# Shield.net
KiCad netlist of a schematic drawn in EAGLE
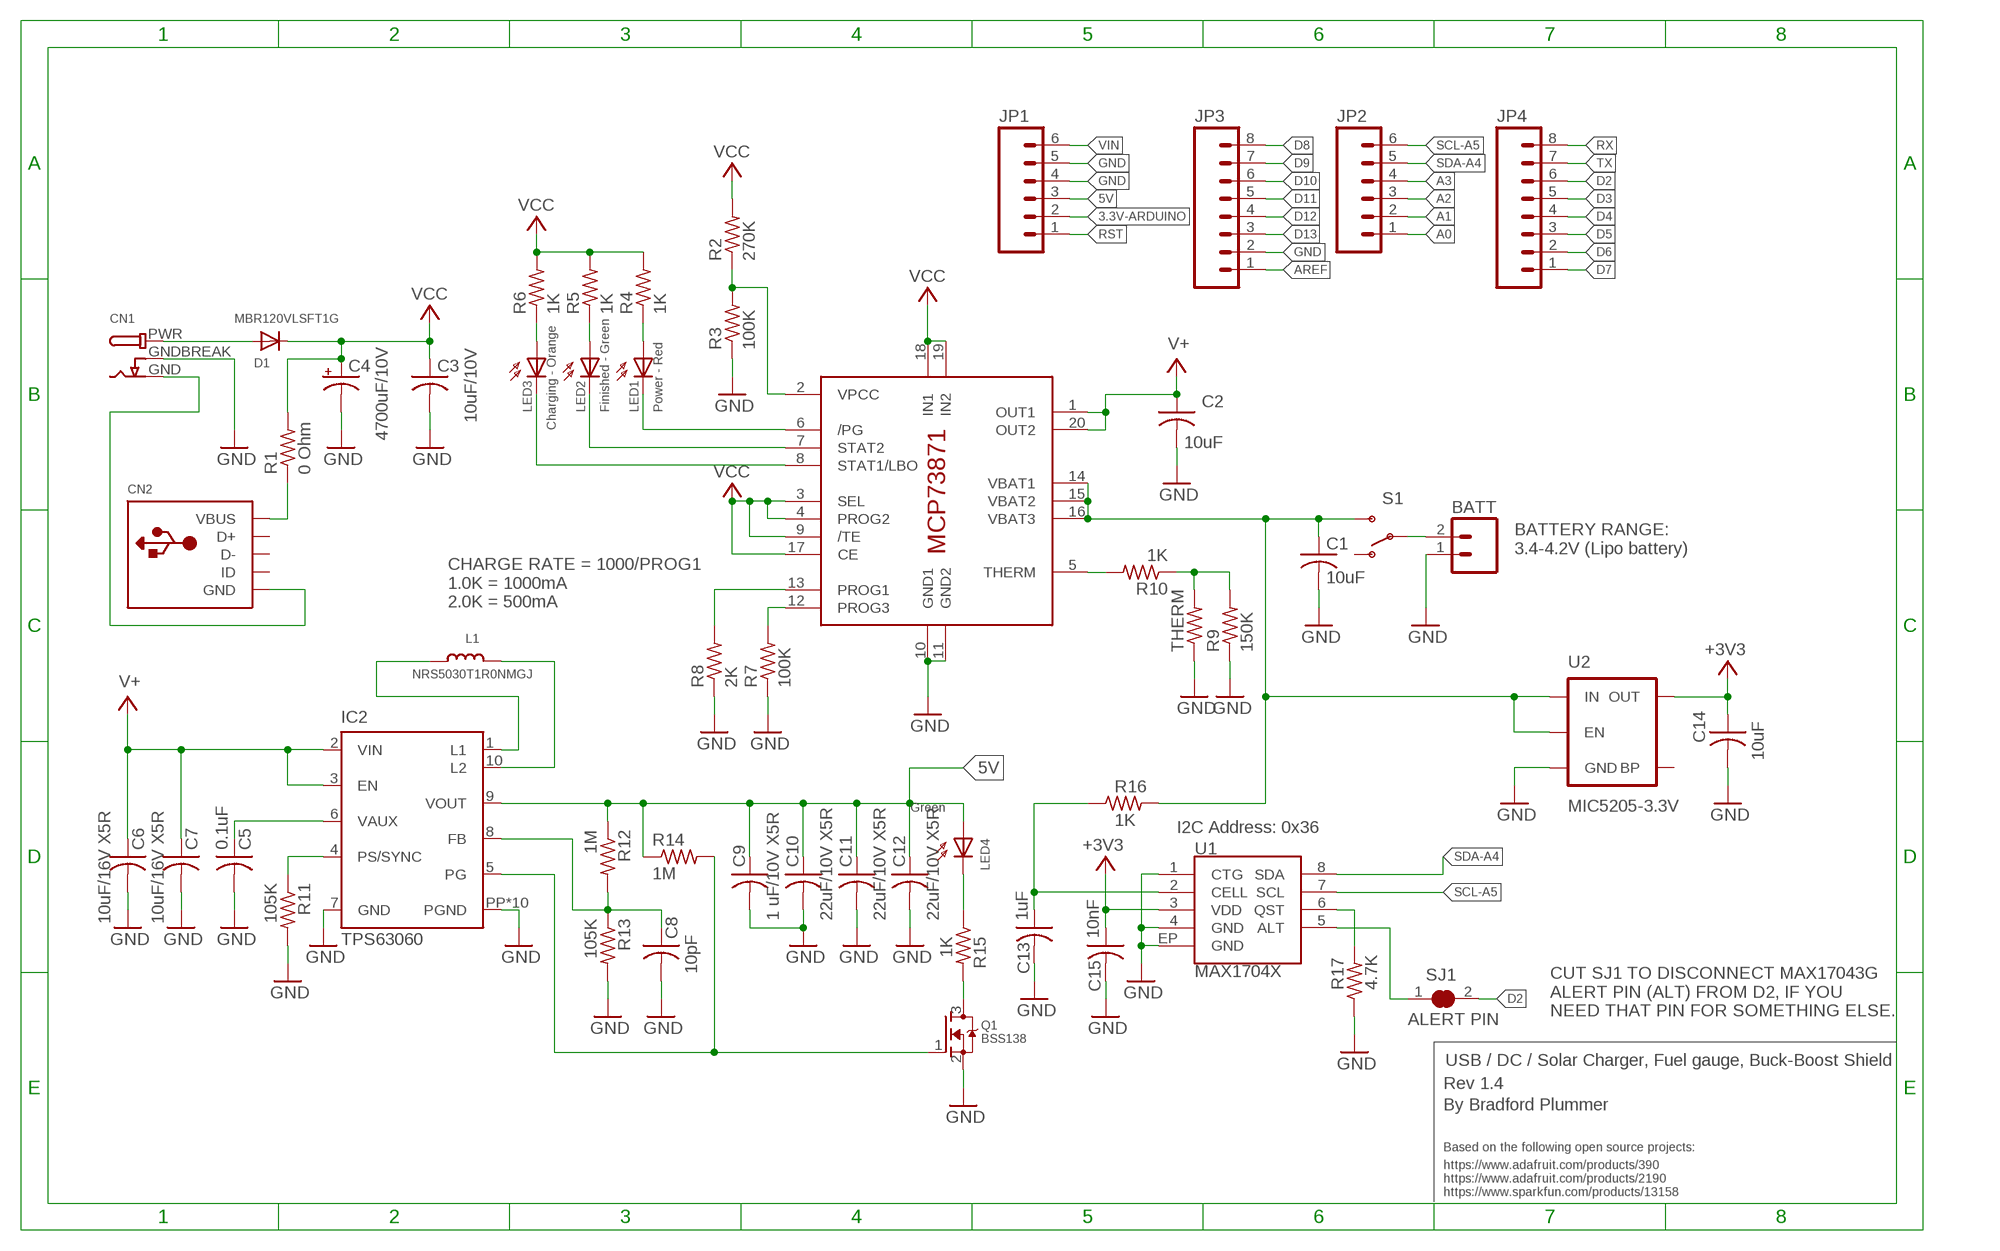
[diagram p0: schematic, sheet 1]

(export (version "E")
  (design (tool "Eeschema 10.0.6"))
  (components
    (comp (ref "BATT")
      (value "M02JST-PTH-VERT")
      (footprint "eagle-import:JST-2-PTH-VERT")
      (libsource (lib "eagle-import") (part "M02JST-PTH-VERT"))
    )
    (comp (ref "C1")
      (value "10uF")
      (footprint "eagle-import:C0805K")
      (libsource (lib "eagle-import") (part "C-USC0805K"))
    )
    (comp (ref "C2")
      (value "10uF")
      (footprint "eagle-import:C0805K")
      (libsource (lib "eagle-import") (part "C-USC0805K"))
    )
    (comp (ref "C3")
      (value "10uF/10V")
      (footprint "eagle-import:C0805K")
      (libsource (lib "eagle-import") (part "C-USC0805K"))
    )
    (comp (ref "C4")
      (value "4700uF/10V")
      (footprint "eagle-import:E5-13")
      (libsource (lib "eagle-import") (part "CPOL-USE5-13"))
    )
    (comp (ref "C5")
      (value "0.1uF")
      (footprint "eagle-import:C0805K")
      (libsource (lib "eagle-import") (part "C-USC0805K"))
    )
    (comp (ref "C6")
      (value "10uF/16V X5R")
      (footprint "eagle-import:C0805K")
      (libsource (lib "eagle-import") (part "C-USC0805K"))
    )
    (comp (ref "C7")
      (value "10uF/16V X5R")
      (footprint "eagle-import:C0805K")
      (libsource (lib "eagle-import") (part "C-USC0805K"))
    )
    (comp (ref "C8")
      (value "10pF")
      (footprint "eagle-import:C0805K")
      (libsource (lib "eagle-import") (part "C-USC0805K"))
    )
    (comp (ref "C9")
      (value "1 uF/10V X5R")
      (footprint "eagle-import:C0805K")
      (libsource (lib "eagle-import") (part "C-USC0805K"))
    )
    (comp (ref "C10")
      (value "22uF/10V X5R")
      (footprint "eagle-import:C0805K")
      (libsource (lib "eagle-import") (part "C-USC0805K"))
    )
    (comp (ref "C11")
      (value "22uF/10V X5R")
      (footprint "eagle-import:C0805K")
      (libsource (lib "eagle-import") (part "C-USC0805K"))
    )
    (comp (ref "C12")
      (value "22uF/10V X5R")
      (footprint "eagle-import:C0805K")
      (libsource (lib "eagle-import") (part "C-USC0805K"))
    )
    (comp (ref "C13")
      (value "1uF")
      (footprint "eagle-import:C0805K")
      (libsource (lib "eagle-import") (part "C-USC0805K"))
    )
    (comp (ref "C14")
      (value "10uF")
      (footprint "eagle-import:C0805K")
      (libsource (lib "eagle-import") (part "C-USC0805K"))
    )
    (comp (ref "C15")
      (value "10nF")
      (footprint "eagle-import:C0805K")
      (libsource (lib "eagle-import") (part "C-USC0805K"))
    )
    (comp (ref "CN1")
      (value "DCBARREL1.3MM")
      (footprint "eagle-import:DCJACK_1.3MM_PTH")
      (libsource (lib "eagle-import") (part "DCBARREL1.3MM"))
    )
    (comp (ref "CN2")
      (value "USBMINIB")
      (footprint "eagle-import:USB-MINIB")
      (libsource (lib "eagle-import") (part "USBMINIB"))
    )
    (comp (ref "D1")
      (value "MBR120VLSFT1G")
      (footprint "eagle-import:SOD-123")
      (libsource (lib "eagle-import") (part "DIODESOD-123"))
    )
    (comp (ref "IC1")
      (value "MCP73871")
      (footprint "eagle-import:QFN20")
      (libsource (lib "eagle-import") (part "MCP73871"))
    )
    (comp (ref "IC2")
      (value "TPS63060")
      (footprint "eagle-import:DSC-S-PWSON-N10")
      (libsource (lib "eagle-import") (part "TPS63060"))
    )
    (comp (ref "JP1")
      (value "M06NO_SILK_FEMALE_PTH")
      (footprint "eagle-import:1X06_NO_SILK")
      (libsource (lib "eagle-import") (part "M06NO_SILK_FEMALE_PTH"))
    )
    (comp (ref "JP2")
      (value "M06NO_SILK_FEMALE_PTH")
      (footprint "eagle-import:1X06_NO_SILK")
      (libsource (lib "eagle-import") (part "M06NO_SILK_FEMALE_PTH"))
    )
    (comp (ref "JP3")
      (value "M08NO_SILK_FEMALE_PTH")
      (footprint "eagle-import:1X08_NO_SILK")
      (libsource (lib "eagle-import") (part "M08NO_SILK_FEMALE_PTH"))
    )
    (comp (ref "JP4")
      (value "M08NO_SILK_FEMALE_PTH")
      (footprint "eagle-import:1X08_NO_SILK")
      (libsource (lib "eagle-import") (part "M08NO_SILK_FEMALE_PTH"))
    )
    (comp (ref "L1")
      (value "NRS5030T1R0NMGJ")
      (footprint "eagle-import:INDUCTOR_5X5MM_TDK_VLC5045")
      (libsource (lib "eagle-import") (part "INDUCTORTDK_VLC5045"))
    )
    (comp (ref "LED1")
      (value "Power - Red")
      (footprint "eagle-import:SFH205")
      (libsource (lib "eagle-import") (part "SFH205"))
    )
    (comp (ref "LED2")
      (value "Finished - Green")
      (footprint "eagle-import:SFH205")
      (libsource (lib "eagle-import") (part "SFH205"))
    )
    (comp (ref "LED3")
      (value "Charging - Orange")
      (footprint "eagle-import:SFH205")
      (libsource (lib "eagle-import") (part "SFH205"))
    )
    (comp (ref "LED4")
      (value "Green")
      (footprint "eagle-import:SFH205")
      (libsource (lib "eagle-import") (part "SFH205"))
    )
    (comp (ref "Q1")
      (value "BSS138")
      (footprint "eagle-import:SOT23-WIDE")
      (libsource (lib "eagle-import") (part "MOSFET-NWIDE"))
    )
    (comp (ref "R1")
      (value "0 Ohm")
      (footprint "eagle-import:R0805")
      (libsource (lib "eagle-import") (part "R-US_R0805"))
    )
    (comp (ref "R2")
      (value "270K")
      (footprint "eagle-import:R0805")
      (libsource (lib "eagle-import") (part "R-US_R0805"))
    )
    (comp (ref "R3")
      (value "100K")
      (footprint "eagle-import:R0805")
      (libsource (lib "eagle-import") (part "R-US_R0805"))
    )
    (comp (ref "R4")
      (value "1K")
      (footprint "eagle-import:R0805")
      (libsource (lib "eagle-import") (part "R-US_R0805"))
    )
    (comp (ref "R5")
      (value "1K")
      (footprint "eagle-import:R0805")
      (libsource (lib "eagle-import") (part "R-US_R0805"))
    )
    (comp (ref "R6")
      (value "1K")
      (footprint "eagle-import:R0805")
      (libsource (lib "eagle-import") (part "R-US_R0805"))
    )
    (comp (ref "R7")
      (value "100K")
      (footprint "eagle-import:R0805")
      (libsource (lib "eagle-import") (part "R-US_R0805"))
    )
    (comp (ref "R8")
      (value "2K")
      (footprint "eagle-import:R0805")
      (libsource (lib "eagle-import") (part "R-US_R0805"))
    )
    (comp (ref "R9")
      (value "150K")
      (footprint "eagle-import:M0805")
      (libsource (lib "eagle-import") (part "R-US_M0805"))
    )
    (comp (ref "R10")
      (value "1K")
      (footprint "eagle-import:M0805")
      (libsource (lib "eagle-import") (part "R-US_M0805"))
    )
    (comp (ref "R11")
      (value "105K")
      (footprint "eagle-import:M0805")
      (libsource (lib "eagle-import") (part "R-US_M0805"))
    )
    (comp (ref "R12")
      (value "1M")
      (footprint "eagle-import:M0805")
      (libsource (lib "eagle-import") (part "R-US_M0805"))
    )
    (comp (ref "R13")
      (value "105K")
      (footprint "eagle-import:M0805")
      (libsource (lib "eagle-import") (part "R-US_M0805"))
    )
    (comp (ref "R14")
      (value "1M")
      (footprint "eagle-import:M0805")
      (libsource (lib "eagle-import") (part "R-US_M0805"))
    )
    (comp (ref "R15")
      (value "1K")
      (footprint "eagle-import:M0805")
      (libsource (lib "eagle-import") (part "R-US_M0805"))
    )
    (comp (ref "R16")
      (value "1K")
      (footprint "eagle-import:M0805")
      (libsource (lib "eagle-import") (part "R-US_M0805"))
    )
    (comp (ref "R17")
      (value "4.7K")
      (footprint "eagle-import:M0805")
      (libsource (lib "eagle-import") (part "R-US_M0805"))
    )
    (comp (ref "S1")
      (value "SWITCH-SPDTPTH")
      (footprint "eagle-import:SWITCH-SPDT")
      (libsource (lib "eagle-import") (part "SWITCH-SPDTPTH"))
    )
    (comp (ref "SJ1")
      (value "ALERT PIN")
      (footprint "eagle-import:SJ")
      (libsource (lib "eagle-import") (part "SJ"))
    )
    (comp (ref "THERM")
      (value "R-US_FLIPFLOP")
      (footprint "eagle-import:0805-THM")
      (libsource (lib "eagle-import") (part "R-US_FLIPFLOP"))
    )
    (comp (ref "U1")
      (value "MAX1704X")
      (footprint "eagle-import:TDFN-8")
      (libsource (lib "eagle-import") (part "MAX1704X"))
    )
    (comp (ref "U2")
      (value "MIC5205-3.3V")
      (footprint "eagle-import:SOT23-5")
      (libsource (lib "eagle-import") (part "MIC52053.3V"))
    )
  )
  (nets
    (net (code "1") (name "+3V3") (class "Default")
      (node (ref "C14") (pin "1") (pinfunction "1_1") (pintype "passive"))
      (node (ref "C15") (pin "1") (pinfunction "1_1") (pintype "passive"))
      (node (ref "U1") (pin "3") (pinfunction "VDD_3") (pintype "bidirectional"))
      (node (ref "U2") (pin "5") (pinfunction "OUT_5") (pintype "passive"))
    )
    (net (code "2") (name "3.3V-ARDUINO") (class "Default")
      (node (ref "JP1") (pin "2") (pinfunction "2_2") (pintype "passive"))
    )
    (net (code "3") (name "5V") (class "Default")
      (node (ref "C10") (pin "1") (pinfunction "1_1") (pintype "passive"))
      (node (ref "C11") (pin "1") (pinfunction "1_1") (pintype "passive"))
      (node (ref "C12") (pin "1") (pinfunction "1_1") (pintype "passive"))
      (node (ref "C9") (pin "1") (pinfunction "1_1") (pintype "passive"))
      (node (ref "IC2") (pin "9") (pinfunction "VOUT_9") (pintype "output"))
      (node (ref "JP1") (pin "3") (pinfunction "3_3") (pintype "passive"))
      (node (ref "LED4") (pin "A") (pinfunction "A_A") (pintype "passive"))
      (node (ref "R12") (pin "1") (pinfunction "1_1") (pintype "passive"))
      (node (ref "R14") (pin "1") (pinfunction "1_1") (pintype "passive"))
    )
    (net (code "4") (name "A0") (class "Default")
      (node (ref "JP2") (pin "1") (pinfunction "1_1") (pintype "passive"))
    )
    (net (code "5") (name "A1") (class "Default")
      (node (ref "JP2") (pin "2") (pinfunction "2_2") (pintype "passive"))
    )
    (net (code "6") (name "A2") (class "Default")
      (node (ref "JP2") (pin "3") (pinfunction "3_3") (pintype "passive"))
    )
    (net (code "7") (name "A3") (class "Default")
      (node (ref "JP2") (pin "4") (pinfunction "4_4") (pintype "passive"))
    )
    (net (code "8") (name "AREF") (class "Default")
      (node (ref "JP3") (pin "1") (pinfunction "1_1") (pintype "passive"))
    )
    (net (code "9") (name "D2") (class "Default")
      (node (ref "JP4") (pin "6") (pinfunction "6_6") (pintype "passive"))
      (node (ref "SJ1") (pin "2") (pinfunction "2_2") (pintype "passive"))
    )
    (net (code "10") (name "D3") (class "Default")
      (node (ref "JP4") (pin "5") (pinfunction "5_5") (pintype "passive"))
    )
    (net (code "11") (name "D4") (class "Default")
      (node (ref "JP4") (pin "4") (pinfunction "4_4") (pintype "passive"))
    )
    (net (code "12") (name "D5") (class "Default")
      (node (ref "JP4") (pin "3") (pinfunction "3_3") (pintype "passive"))
    )
    (net (code "13") (name "D6") (class "Default")
      (node (ref "JP4") (pin "2") (pinfunction "2_2") (pintype "passive"))
    )
    (net (code "14") (name "D7") (class "Default")
      (node (ref "JP4") (pin "1") (pinfunction "1_1") (pintype "passive"))
    )
    (net (code "15") (name "D8") (class "Default")
      (node (ref "JP3") (pin "8") (pinfunction "8_8") (pintype "passive"))
    )
    (net (code "16") (name "D9") (class "Default")
      (node (ref "JP3") (pin "7") (pinfunction "7_7") (pintype "passive"))
    )
    (net (code "17") (name "D10") (class "Default")
      (node (ref "JP3") (pin "6") (pinfunction "6_6") (pintype "passive"))
    )
    (net (code "18") (name "D11") (class "Default")
      (node (ref "JP3") (pin "5") (pinfunction "5_5") (pintype "passive"))
    )
    (net (code "19") (name "D12") (class "Default")
      (node (ref "JP3") (pin "4") (pinfunction "4_4") (pintype "passive"))
    )
    (net (code "20") (name "D13") (class "Default")
      (node (ref "JP3") (pin "3") (pinfunction "3_3") (pintype "passive"))
    )
    (net (code "21") (name "GND") (class "Default")
      (node (ref "BATT") (pin "1") (pinfunction "1_1") (pintype "passive"))
      (node (ref "C1") (pin "2") (pinfunction "2_2") (pintype "passive"))
      (node (ref "C10") (pin "2") (pinfunction "2_2") (pintype "passive"))
      (node (ref "C11") (pin "2") (pinfunction "2_2") (pintype "passive"))
      (node (ref "C12") (pin "2") (pinfunction "2_2") (pintype "passive"))
      (node (ref "C13") (pin "2") (pinfunction "2_2") (pintype "passive"))
      (node (ref "C14") (pin "2") (pinfunction "2_2") (pintype "passive"))
      (node (ref "C15") (pin "2") (pinfunction "2_2") (pintype "passive"))
      (node (ref "C2") (pin "2") (pinfunction "2_2") (pintype "passive"))
      (node (ref "C3") (pin "2") (pinfunction "2_2") (pintype "passive"))
      (node (ref "C4") (pin "-") (pinfunction "-_-") (pintype "passive"))
      (node (ref "C5") (pin "2") (pinfunction "2_2") (pintype "passive"))
      (node (ref "C6") (pin "2") (pinfunction "2_2") (pintype "passive"))
      (node (ref "C7") (pin "2") (pinfunction "2_2") (pintype "passive"))
      (node (ref "C8") (pin "2") (pinfunction "2_2") (pintype "passive"))
      (node (ref "C9") (pin "2") (pinfunction "2_2") (pintype "passive"))
      (node (ref "CN1") (pin "GNDBREAK") (pinfunction "GNDBREAK_GNDBREAK") (pintype "power_in"))
      (node (ref "IC1") (pin "10") (pinfunction "GND1_10") (pintype "power_in"))
      (node (ref "IC1") (pin "11") (pinfunction "GND2_11") (pintype "power_in"))
      (node (ref "IC2") (pin "7") (pinfunction "GND_7") (pintype "input"))
      (node (ref "IC2") (pin "PP") (pinfunction "PGND_PP") (pintype "power_in"))
      (node (ref "IC2") (pin "PP@1") (pinfunction "PGND_PP@1") (pintype "power_in"))
      (node (ref "IC2") (pin "PP@10") (pinfunction "PGND_PP@10") (pintype "power_in"))
      (node (ref "IC2") (pin "PP@2") (pinfunction "PGND_PP@2") (pintype "power_in"))
      (node (ref "IC2") (pin "PP@3") (pinfunction "PGND_PP@3") (pintype "power_in"))
      (node (ref "IC2") (pin "PP@4") (pinfunction "PGND_PP@4") (pintype "power_in"))
      (node (ref "IC2") (pin "PP@5") (pinfunction "PGND_PP@5") (pintype "power_in"))
      (node (ref "IC2") (pin "PP@7") (pinfunction "PGND_PP@7") (pintype "power_in"))
      (node (ref "IC2") (pin "PP@8") (pinfunction "PGND_PP@8") (pintype "power_in"))
      (node (ref "IC2") (pin "PP@9") (pinfunction "PGND_PP@9") (pintype "power_in"))
      (node (ref "JP1") (pin "4") (pinfunction "4_4") (pintype "passive"))
      (node (ref "JP1") (pin "5") (pinfunction "5_5") (pintype "passive"))
      (node (ref "JP3") (pin "2") (pinfunction "2_2") (pintype "passive"))
      (node (ref "Q1") (pin "2") (pinfunction "S_2") (pintype "bidirectional"))
      (node (ref "R11") (pin "2") (pinfunction "2_2") (pintype "passive"))
      (node (ref "R13") (pin "2") (pinfunction "2_2") (pintype "passive"))
      (node (ref "R17") (pin "1") (pinfunction "1_1") (pintype "passive"))
      (node (ref "R3") (pin "1") (pinfunction "1_1") (pintype "passive"))
      (node (ref "R7") (pin "1") (pinfunction "1_1") (pintype "passive"))
      (node (ref "R8") (pin "1") (pinfunction "1_1") (pintype "passive"))
      (node (ref "R9") (pin "1") (pinfunction "1_1") (pintype "passive"))
      (node (ref "THERM") (pin "1") (pinfunction "1_1") (pintype "passive"))
      (node (ref "U1") (pin "1") (pinfunction "CTG_1") (pintype "bidirectional"))
      (node (ref "U1") (pin "4") (pinfunction "GND_4") (pintype "bidirectional"))
      (node (ref "U1") (pin "EP") (pinfunction "GND_EP") (pintype "bidirectional"))
      (node (ref "U2") (pin "2") (pinfunction "GND_2") (pintype "input"))
    )
    (net (code "22") (name "Net-(CN1-PadGND)") (class "Default")
      (node (ref "CN1") (pin "GND") (pinfunction "GND_GND") (pintype "power_in"))
      (node (ref "CN2") (pin "GND") (pinfunction "GND_GND") (pintype "power_in"))
    )
    (net (code "23") (name "Net-(CN1-PadPWR)") (class "Default")
      (node (ref "CN1") (pin "PWR") (pinfunction "PWR_PWR") (pintype "power_in"))
      (node (ref "D1") (pin "A") (pinfunction "A_A") (pintype "passive"))
    )
    (net (code "24") (name "Net-(CN2-PadVBUS)") (class "Default")
      (node (ref "CN2") (pin "VBUS") (pinfunction "VBUS_VBUS") (pintype "power_in"))
      (node (ref "R1") (pin "1") (pinfunction "1_1") (pintype "passive"))
    )
    (net (code "25") (name "Net-(IC1-PROG1)") (class "Default")
      (node (ref "IC1") (pin "13") (pinfunction "PROG1_13") (pintype "input"))
      (node (ref "R8") (pin "2") (pinfunction "2_2") (pintype "passive"))
    )
    (net (code "26") (name "Net-(IC1-PROG3)") (class "Default")
      (node (ref "IC1") (pin "12") (pinfunction "PROG3_12") (pintype "input"))
      (node (ref "R7") (pin "2") (pinfunction "2_2") (pintype "passive"))
    )
    (net (code "27") (name "Net-(IC1-STAT1{slash}LBO)") (class "Default")
      (node (ref "IC1") (pin "8") (pinfunction "STAT1/LBO_8") (pintype "output"))
      (node (ref "LED3") (pin "K") (pinfunction "C_K") (pintype "passive"))
    )
    (net (code "28") (name "Net-(IC1-STAT2)") (class "Default")
      (node (ref "IC1") (pin "7") (pinfunction "STAT2_7") (pintype "output"))
      (node (ref "LED2") (pin "K") (pinfunction "C_K") (pintype "passive"))
    )
    (net (code "29") (name "Net-(IC1-THERM)") (class "Default")
      (node (ref "IC1") (pin "5") (pinfunction "THERM_5") (pintype "input"))
      (node (ref "R10") (pin "2") (pinfunction "2_2") (pintype "passive"))
    )
    (net (code "30") (name "Net-(IC1-VBAT1)") (class "Default")
      (node (ref "C1") (pin "1") (pinfunction "1_1") (pintype "passive"))
      (node (ref "IC1") (pin "14") (pinfunction "VBAT1_14") (pintype "output"))
      (node (ref "IC1") (pin "15") (pinfunction "VBAT2_15") (pintype "output"))
      (node (ref "IC1") (pin "16") (pinfunction "VBAT3_16") (pintype "output"))
      (node (ref "R16") (pin "2") (pinfunction "2_2") (pintype "passive"))
      (node (ref "S1") (pin "3") (pinfunction "S_3") (pintype "passive"))
      (node (ref "U2") (pin "1") (pinfunction "IN_1") (pintype "input"))
      (node (ref "U2") (pin "3") (pinfunction "EN_3") (pintype "input"))
    )
    (net (code "31") (name "Net-(IC1-VPCC)") (class "Default")
      (node (ref "IC1") (pin "2") (pinfunction "VPCC_2") (pintype "input"))
      (node (ref "R2") (pin "1") (pinfunction "1_1") (pintype "passive"))
      (node (ref "R3") (pin "2") (pinfunction "2_2") (pintype "passive"))
    )
    (net (code "32") (name "Net-(IC1-{slash}PG)") (class "Default")
      (node (ref "IC1") (pin "6") (pinfunction "/PG_6") (pintype "output"))
      (node (ref "LED1") (pin "K") (pinfunction "C_K") (pintype "passive"))
    )
    (net (code "33") (name "Net-(IC2-FB)") (class "Default")
      (node (ref "C8") (pin "1") (pinfunction "1_1") (pintype "passive"))
      (node (ref "IC2") (pin "8") (pinfunction "FB_8") (pintype "input"))
      (node (ref "R12") (pin "2") (pinfunction "2_2") (pintype "passive"))
      (node (ref "R13") (pin "1") (pinfunction "1_1") (pintype "passive"))
    )
    (net (code "34") (name "Net-(IC2-L1)") (class "Default")
      (node (ref "IC2") (pin "1") (pinfunction "L1_1") (pintype "input"))
      (node (ref "L1") (pin "P$1") (pinfunction "1_P$1") (pintype "passive"))
    )
    (net (code "35") (name "Net-(IC2-L2)") (class "Default")
      (node (ref "IC2") (pin "10") (pinfunction "L2_10") (pintype "input"))
      (node (ref "L1") (pin "P$2") (pinfunction "2_P$2") (pintype "passive"))
    )
    (net (code "36") (name "Net-(IC2-PG)") (class "Default")
      (node (ref "IC2") (pin "5") (pinfunction "PG_5") (pintype "output"))
      (node (ref "Q1") (pin "1") (pinfunction "G_1") (pintype "bidirectional"))
      (node (ref "R14") (pin "2") (pinfunction "2_2") (pintype "passive"))
    )
    (net (code "37") (name "Net-(IC2-PS{slash}SYNC)") (class "Default")
      (node (ref "IC2") (pin "4") (pinfunction "PS/SYNC_4") (pintype "input"))
      (node (ref "R11") (pin "1") (pinfunction "1_1") (pintype "passive"))
    )
    (net (code "38") (name "Net-(IC2-VAUX)") (class "Default")
      (node (ref "C5") (pin "1") (pinfunction "1_1") (pintype "passive"))
      (node (ref "IC2") (pin "6") (pinfunction "VAUX_6") (pintype "power_in"))
    )
    (net (code "39") (name "Net-(LED1-PadA)") (class "Default")
      (node (ref "LED1") (pin "A") (pinfunction "A_A") (pintype "passive"))
      (node (ref "R4") (pin "1") (pinfunction "1_1") (pintype "passive"))
    )
    (net (code "40") (name "Net-(LED2-PadA)") (class "Default")
      (node (ref "LED2") (pin "A") (pinfunction "A_A") (pintype "passive"))
      (node (ref "R5") (pin "1") (pinfunction "1_1") (pintype "passive"))
    )
    (net (code "41") (name "Net-(LED3-PadA)") (class "Default")
      (node (ref "LED3") (pin "A") (pinfunction "A_A") (pintype "passive"))
      (node (ref "R6") (pin "1") (pinfunction "1_1") (pintype "passive"))
    )
    (net (code "42") (name "Net-(LED4-C)") (class "Default")
      (node (ref "LED4") (pin "K") (pinfunction "C_K") (pintype "passive"))
      (node (ref "R15") (pin "1") (pinfunction "1_1") (pintype "passive"))
    )
    (net (code "43") (name "Net-(Q1-D)") (class "Default")
      (node (ref "Q1") (pin "3") (pinfunction "D_3") (pintype "bidirectional"))
      (node (ref "R15") (pin "2") (pinfunction "2_2") (pintype "passive"))
    )
    (net (code "44") (name "Net-(R10-Pad1)") (class "Default")
      (node (ref "R10") (pin "1") (pinfunction "1_1") (pintype "passive"))
      (node (ref "R9") (pin "2") (pinfunction "2_2") (pintype "passive"))
      (node (ref "THERM") (pin "2") (pinfunction "2_2") (pintype "passive"))
    )
    (net (code "45") (name "Net-(S1-P)") (class "Default")
      (node (ref "BATT") (pin "2") (pinfunction "2_2") (pintype "passive"))
      (node (ref "S1") (pin "2") (pinfunction "P_2") (pintype "passive"))
    )
    (net (code "46") (name "Net-(U1-ALT)") (class "Default")
      (node (ref "SJ1") (pin "1") (pinfunction "1_1") (pintype "passive"))
      (node (ref "U1") (pin "5") (pinfunction "ALT_5") (pintype "bidirectional"))
    )
    (net (code "47") (name "Net-(U1-CELL)") (class "Default")
      (node (ref "C13") (pin "1") (pinfunction "1_1") (pintype "passive"))
      (node (ref "R16") (pin "1") (pinfunction "1_1") (pintype "passive"))
      (node (ref "U1") (pin "2") (pinfunction "CELL_2") (pintype "bidirectional"))
    )
    (net (code "48") (name "Net-(U1-QST)") (class "Default")
      (node (ref "R17") (pin "2") (pinfunction "2_2") (pintype "passive"))
      (node (ref "U1") (pin "6") (pinfunction "QST_6") (pintype "bidirectional"))
    )
    (net (code "49") (name "RST") (class "Default")
      (node (ref "JP1") (pin "1") (pinfunction "1_1") (pintype "passive"))
    )
    (net (code "50") (name "RX") (class "Default")
      (node (ref "JP4") (pin "8") (pinfunction "8_8") (pintype "passive"))
    )
    (net (code "51") (name "SCL-A5") (class "Default")
      (node (ref "JP2") (pin "6") (pinfunction "6_6") (pintype "passive"))
      (node (ref "U1") (pin "7") (pinfunction "SCL_7") (pintype "bidirectional"))
    )
    (net (code "52") (name "SDA-A4") (class "Default")
      (node (ref "JP2") (pin "5") (pinfunction "5_5") (pintype "passive"))
      (node (ref "U1") (pin "8") (pinfunction "SDA_8") (pintype "bidirectional"))
    )
    (net (code "53") (name "TX") (class "Default")
      (node (ref "JP4") (pin "7") (pinfunction "7_7") (pintype "passive"))
    )
    (net (code "54") (name "V+") (class "Default")
      (node (ref "C2") (pin "1") (pinfunction "1_1") (pintype "passive"))
      (node (ref "C6") (pin "1") (pinfunction "1_1") (pintype "passive"))
      (node (ref "C7") (pin "1") (pinfunction "1_1") (pintype "passive"))
      (node (ref "IC1") (pin "1") (pinfunction "OUT1_1") (pintype "output"))
      (node (ref "IC1") (pin "20") (pinfunction "OUT2_20") (pintype "output"))
      (node (ref "IC2") (pin "2") (pinfunction "VIN_2") (pintype "input"))
      (node (ref "IC2") (pin "3") (pinfunction "EN_3") (pintype "input"))
    )
    (net (code "55") (name "VCC") (class "Default")
      (node (ref "C3") (pin "1") (pinfunction "1_1") (pintype "passive"))
      (node (ref "C4") (pin "+") (pinfunction "+_+") (pintype "passive"))
      (node (ref "D1") (pin "C") (pinfunction "C_C") (pintype "passive"))
      (node (ref "IC1") (pin "17") (pinfunction "CE_17") (pintype "input"))
      (node (ref "IC1") (pin "18") (pinfunction "IN1_18") (pintype "input"))
      (node (ref "IC1") (pin "19") (pinfunction "IN2_19") (pintype "input"))
      (node (ref "IC1") (pin "3") (pinfunction "SEL_3") (pintype "input"))
      (node (ref "IC1") (pin "4") (pinfunction "PROG2_4") (pintype "input"))
      (node (ref "IC1") (pin "9") (pinfunction "/TE_9") (pintype "input"))
      (node (ref "R1") (pin "2") (pinfunction "2_2") (pintype "passive"))
      (node (ref "R2") (pin "2") (pinfunction "2_2") (pintype "passive"))
      (node (ref "R4") (pin "2") (pinfunction "2_2") (pintype "passive"))
      (node (ref "R5") (pin "2") (pinfunction "2_2") (pintype "passive"))
      (node (ref "R6") (pin "2") (pinfunction "2_2") (pintype "passive"))
    )
    (net (code "56") (name "VIN") (class "Default")
      (node (ref "JP1") (pin "6") (pinfunction "6_6") (pintype "passive"))
    )
    (net (code "57") (name "unconnected-(CN2-PadD+)") (class "Default")
      (node (ref "CN2") (pin "D+") (pinfunction "D+_D+") (pintype "bidirectional"))
    )
    (net (code "58") (name "unconnected-(CN2-PadD-)") (class "Default")
      (node (ref "CN2") (pin "D-") (pinfunction "D-_D-") (pintype "bidirectional"))
    )
    (net (code "59") (name "unconnected-(CN2-PadID)") (class "Default")
      (node (ref "CN2") (pin "ID") (pinfunction "ID_ID") (pintype "bidirectional"))
    )
    (net (code "60") (name "unconnected-(S1-O-Pad1)") (class "Default")
      (node (ref "S1") (pin "1") (pinfunction "O_1") (pintype "passive"))
    )
    (net (code "61") (name "unconnected-(U2-BP-Pad4)") (class "Default")
      (node (ref "U2") (pin "4") (pinfunction "BP_4") (pintype "input"))
    )
  )
)
